# compute_module_USB.net
KiCad netlist of a schematic drawn in Altium Designer
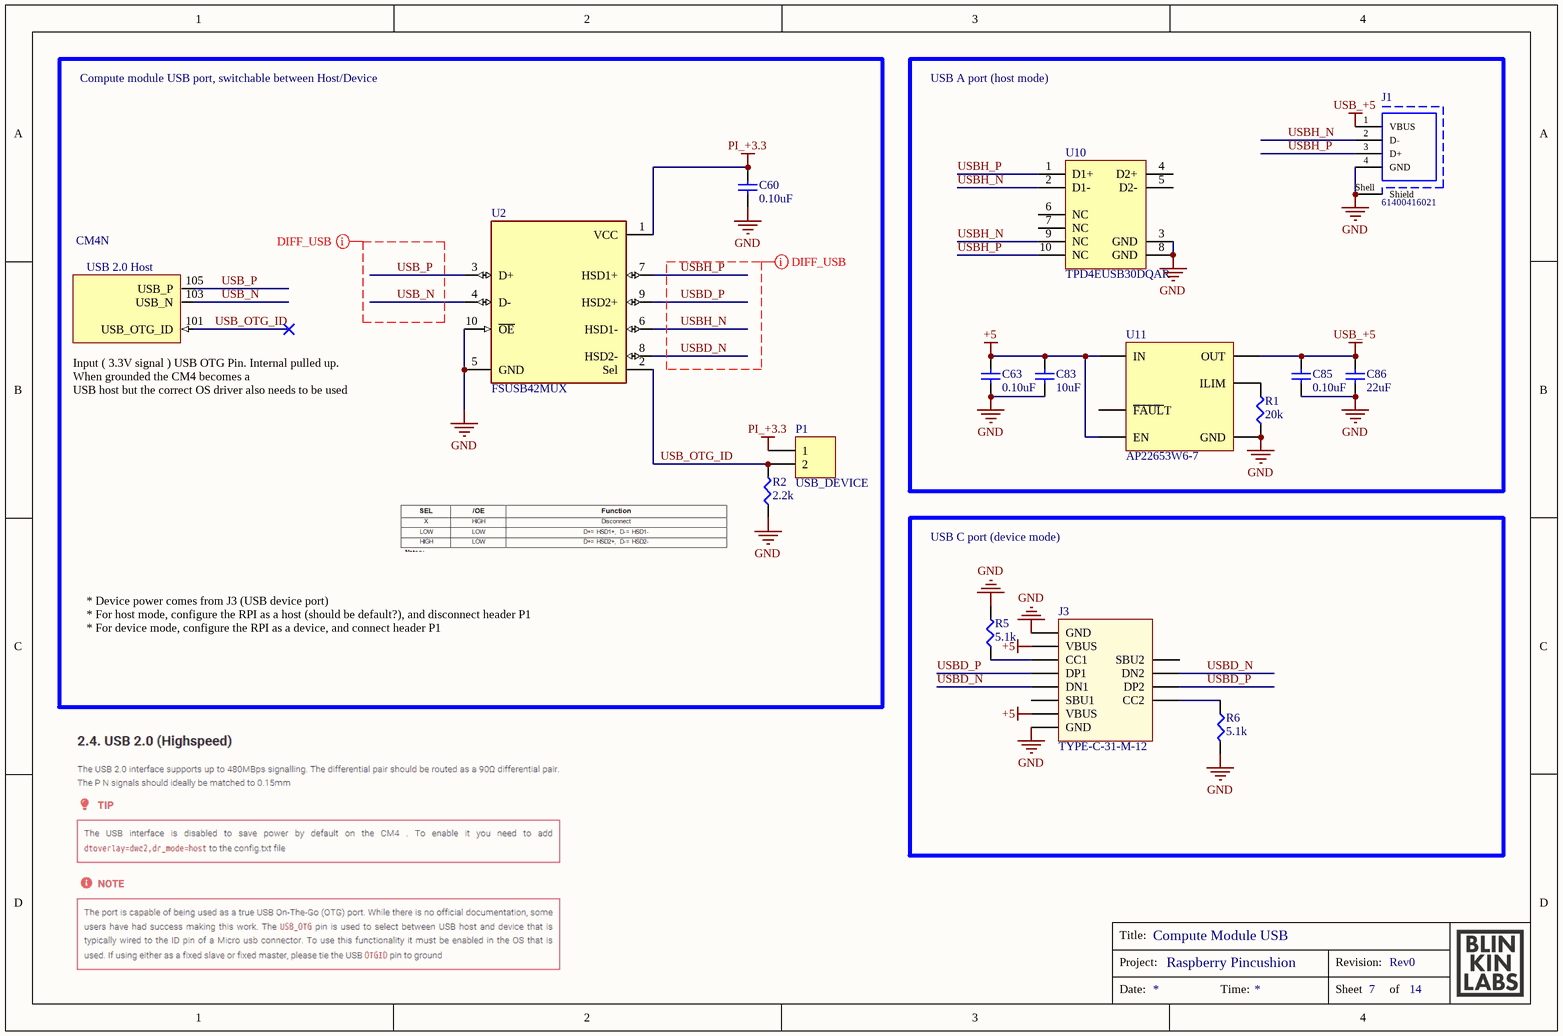
[diagram p0: compute module USB.SchDoc]

(export (version "E")
  (design (tool "Eeschema 10.0.6"))
  (components
    (comp (ref "C60")
      (value "0.10uF")
      (footprint "CAPC1005X06L")
      (description "CAP CER 0.1UF 10V X5R 0402")
      (fields
        (field (name "PARTNUMBER") "GRM155R61A104KA01D")
        (field (name "DIGI-KEY PART NUMBER") "490-1318-1-ND")
      )
      (libsource (lib "cap_murata") (part "CAPACITOR"))
    )
    (comp (ref "C63")
      (value "0.10uF")
      (footprint "CAPC1005X06L")
      (description "CAP CER 0.1UF 10V X5R 0402")
      (fields
        (field (name "PARTNUMBER") "GRM155R61A104KA01D")
        (field (name "DIGI-KEY PART NUMBER") "490-1318-1-ND")
      )
      (libsource (lib "cap_murata") (part "CAPACITOR"))
    )
    (comp (ref "C83")
      (value "10uF")
      (footprint "CAPC2012X10L")
      (description "CAP CER 10UF 10V X7R 0805")
      (fields
        (field (name "PARTNUMBER") "GRM21BR71A106KE51L")
        (field (name "DIGI-KEY PART NUMBER") "490-3905-1-ND")
      )
      (libsource (lib "cap_murata") (part "CAPACITOR"))
    )
    (comp (ref "C85")
      (value "0.10uF")
      (footprint "CAPC1005X06L")
      (description "CAP CER 0.1UF 10V X5R 0402")
      (fields
        (field (name "PARTNUMBER") "GRM155R61A104KA01D")
        (field (name "DIGI-KEY PART NUMBER") "490-1318-1-ND")
      )
      (libsource (lib "cap_murata") (part "CAPACITOR"))
    )
    (comp (ref "C86")
      (value "22uF")
      (footprint "CAPC2012X10L")
      (description "CAP CER 22UF 10V X5R 0805")
      (fields
        (field (name "PARTNUMBER") "GRM219R61A226MEA0D")
        (field (name "DIGI-KEY PART NUMBER") "490-9951-1-ND")
      )
      (libsource (lib "cap_murata") (part "CAPACITOR"))
    )
    (comp (ref "CM4")
      (value "Raspberry Pi Compute Module 4")
      (footprint "CM4-F40C-100DS-0.4v_1.5mm_0mm")
      (description "Raspberry Pi Compute Module 4 by Amornthep Phunsin")
      (libsource (lib "CM4") (part "CM4"))
    )
    (comp (ref "J1")
      (value "61400416021")
      (footprint "61400416021")
      (description "USB 2.0 Type A Receptacle WR-COM, Horizontal, THT")
      (fields (field (name "MANUFACTURER") "Wurth Elektronik") (field (name "PUBLISHER") "WurthElektronik"))
      (libsource (lib "Altium Content Vault") (part "WE-USB-4-1SHLD"))
    )
    (comp (ref "J3")
      (value "TYPE-C-31-M-12")
      (footprint "TYPE-C-31-M-12")
      (description "USB Connector TYPE-C-31-M-12 Female 16P SMD")
      (fields (field (name "MANUFACTURER") "HRO"))
      (libsource (lib "Blinkinlabs") (part "TYPE-C-31-M-12"))
    )
    (comp (ref "P1")
      (value "USB_DEVICE")
      (footprint "HDR1X2")
      (description "Header, 2-Pin")
      (fields (field (name "PUBLISHER") "Altium Limited"))
      (libsource (lib "Miscellaneous Connectors") (part "Header 2"))
    )
    (comp (ref "R1")
      (value "20k")
      (footprint "ERJ2G(0402)_L")
      (description "RES SMD 20K OHM 1% 1/10W 0402")
      (fields
        (field (name "PARTNUMBER") "ERJ-2RKF2002X")
        (field (name "DIGI-KEY PART NUMBER") "P20.0KLCT-ND")
      )
      (libsource (lib "res_panasonic_erj_xls") (part "RESISTOR"))
    )
    (comp (ref "R2")
      (value "2.2k")
      (footprint "ERJ2G(0402)_L")
      (description "RES SMD 2.2K OHM 1% 1/10W 0402")
      (fields
        (field (name "PARTNUMBER") "ERJ-2RKF2201X")
        (field (name "DIGI-KEY PART NUMBER") "P2.20KLCT-ND")
      )
      (libsource (lib "res_panasonic_erj_xls") (part "RESISTOR"))
    )
    (comp (ref "R5")
      (value "5.1k")
      (footprint "ERJ2G(0402)_N")
      (description "RES SMD 5.1K OHM 1% 1/10W 0402")
      (fields
        (field (name "PARTNUMBER") "ERJ-2RKF5101X")
        (field (name "DIGI-KEY PART NUMBER") "P5.10KLCT-ND")
      )
      (libsource (lib "res_panasonic_erj_xls") (part "RESISTOR"))
    )
    (comp (ref "R6")
      (value "5.1k")
      (footprint "ERJ2G(0402)_N")
      (description "RES SMD 5.1K OHM 1% 1/10W 0402")
      (fields
        (field (name "PARTNUMBER") "ERJ-2RKF5101X")
        (field (name "DIGI-KEY PART NUMBER") "P5.10KLCT-ND")
      )
      (libsource (lib "res_panasonic_erj_xls") (part "RESISTOR"))
    )
    (comp (ref "U2")
      (value "FSUSB42MUX")
      (footprint "FP-846AP-MFG")
      (description "IC USB SWITCH DPDT 10MSOP")
      (fields (field (name "VOLTAGE") "4.3V"))
      (libsource (lib "Altium Content Vault") (part "e0bd5e1b4e0e4edc77f3356c64bf8f9"))
    )
    (comp (ref "U10")
      (value "TPD4EUSB30DQAR")
      (footprint "DQA0010A_V")
      (fields (field (name "MANUFACTURER") "Texas Instruments"))
      (libsource (lib "Altium Content Vault") (part "TI-TPD4EUSB30-SON_DQA-10"))
    )
    (comp (ref "U11")
      (value "AP22653W6-7")
      (footprint "SOT95P280X145-6N-5")
      (description "LOAD SWITCH,SOT26,T&R,3K")
      (fields
        (field (name "MANUFACTURER") "Diodes Incorporated")
        (field (name "DIGIKEY PARTNUMBER") "31-AP22653W6-7TR-ND")
      )
      (libsource (lib "Blinkinlabs") (part "AP22653W6-7"))
    )
  )
  (nets
    (net (code "1") (name "+5") (class "Default")
      (node (ref "C63") (pin "2") (pinfunction "2_2") (pintype "passive"))
      (node (ref "C83") (pin "1") (pinfunction "1_1") (pintype "passive"))
      (node (ref "J3") (pin "A4/B9") (pinfunction "VBUS_A4/B9") (pintype "passive"))
      (node (ref "J3") (pin "A9/B4") (pinfunction "VBUS_A9/B4") (pintype "passive"))
      (node (ref "U11") (pin "1") (pinfunction "IN_1") (pintype "passive"))
      (node (ref "U11") (pin "3") (pinfunction "EN_3") (pintype "passive"))
    )
    (net (code "2") (name "/USBD_N") (class "Default")
      (node (ref "J3") (pin "A7") (pinfunction "DN1_A7") (pintype "passive"))
      (node (ref "J3") (pin "B7") (pinfunction "DN2_B7") (pintype "passive"))
      (node (ref "U2") (pin "8") (pinfunction "HSD2-_8") (pintype "bidirectional"))
    )
    (net (code "3") (name "/USBD_P") (class "Default")
      (node (ref "J3") (pin "A6") (pinfunction "DP1_A6") (pintype "passive"))
      (node (ref "J3") (pin "B6") (pinfunction "DP2_B6") (pintype "passive"))
      (node (ref "U2") (pin "9") (pinfunction "HSD2+_9") (pintype "bidirectional"))
    )
    (net (code "4") (name "/USBH_N") (class "Default")
      (node (ref "J1") (pin "2") (pinfunction "D-_2") (pintype "passive"))
      (node (ref "U10") (pin "2") (pinfunction "D1-_2") (pintype "passive"))
      (node (ref "U10") (pin "9") (pinfunction "NC_9") (pintype "passive"))
      (node (ref "U2") (pin "6") (pinfunction "HSD1-_6") (pintype "bidirectional"))
    )
    (net (code "5") (name "/USBH_P") (class "Default")
      (node (ref "J1") (pin "3") (pinfunction "D+_3") (pintype "passive"))
      (node (ref "U10") (pin "1") (pinfunction "D1+_1") (pintype "passive"))
      (node (ref "U10") (pin "10") (pinfunction "NC_10") (pintype "passive"))
      (node (ref "U2") (pin "7") (pinfunction "HSD1+_7") (pintype "bidirectional"))
    )
    (net (code "6") (name "/USB_N") (class "Default")
      (node (ref "CM4") (pin "103") (pinfunction "USB_N_103") (pintype "passive"))
      (node (ref "U2") (pin "4") (pinfunction "D-_4") (pintype "bidirectional"))
    )
    (net (code "7") (name "/USB_OTG_ID") (class "Default")
      (node (ref "CM4") (pin "101") (pinfunction "USB_OTG_ID_101") (pintype "input"))
      (node (ref "P1") (pin "2") (pinfunction "2_2") (pintype "passive"))
      (node (ref "R2") (pin "2") (pinfunction "2_2") (pintype "passive"))
      (node (ref "U2") (pin "2") (pinfunction "Sel_2") (pintype "passive"))
    )
    (net (code "8") (name "/USB_P") (class "Default")
      (node (ref "CM4") (pin "105") (pinfunction "USB_P_105") (pintype "passive"))
      (node (ref "U2") (pin "3") (pinfunction "D+_3") (pintype "bidirectional"))
    )
    (net (code "9") (name "GND") (class "Default")
      (node (ref "C60") (pin "1") (pinfunction "1_1") (pintype "passive"))
      (node (ref "C63") (pin "1") (pinfunction "1_1") (pintype "passive"))
      (node (ref "C83") (pin "2") (pinfunction "2_2") (pintype "passive"))
      (node (ref "C85") (pin "1") (pinfunction "1_1") (pintype "passive"))
      (node (ref "C86") (pin "2") (pinfunction "2_2") (pintype "passive"))
      (node (ref "J1") (pin "4") (pinfunction "GND_4") (pintype "passive"))
      (node (ref "J1") (pin "Shell") (pinfunction "Shield_Shell") (pintype "passive"))
      (node (ref "J3") (pin "A1/B12") (pinfunction "GND_A1/B12") (pintype "passive"))
      (node (ref "J3") (pin "A12/B1") (pinfunction "GND_A12/B1") (pintype "passive"))
      (node (ref "R1") (pin "1") (pinfunction "1_1") (pintype "passive"))
      (node (ref "R2") (pin "1") (pinfunction "1_1") (pintype "passive"))
      (node (ref "R5") (pin "2") (pinfunction "2_2") (pintype "passive"))
      (node (ref "R6") (pin "2") (pinfunction "2_2") (pintype "passive"))
      (node (ref "U10") (pin "3") (pinfunction "GND_3") (pintype "power_in"))
      (node (ref "U10") (pin "8") (pinfunction "GND_8") (pintype "power_in"))
      (node (ref "U11") (pin "2") (pinfunction "GND_2") (pintype "passive"))
      (node (ref "U2") (pin "10") (pinfunction "~{OE}_10") (pintype "input"))
      (node (ref "U2") (pin "5") (pinfunction "GND_5") (pintype "power_in"))
    )
    (net (code "10") (name "Net-(J3-CC1)") (class "Default")
      (node (ref "J3") (pin "A5") (pinfunction "CC1_A5") (pintype "passive"))
      (node (ref "R5") (pin "1") (pinfunction "1_1") (pintype "passive"))
    )
    (net (code "11") (name "Net-(J3-CC2)") (class "Default")
      (node (ref "J3") (pin "B5") (pinfunction "CC2_B5") (pintype "passive"))
      (node (ref "R6") (pin "1") (pinfunction "1_1") (pintype "passive"))
    )
    (net (code "12") (name "Net-(U11-ILIM)") (class "Default")
      (node (ref "R1") (pin "2") (pinfunction "2_2") (pintype "passive"))
      (node (ref "U11") (pin "5") (pinfunction "ILIM_5") (pintype "passive"))
    )
    (net (code "13") (name "PI_+3.3") (class "Default")
      (node (ref "C60") (pin "2") (pinfunction "2_2") (pintype "passive"))
      (node (ref "P1") (pin "1") (pinfunction "1_1") (pintype "passive"))
      (node (ref "U2") (pin "1") (pinfunction "VCC_1") (pintype "power_in"))
    )
    (net (code "14") (name "USB_+5") (class "Default")
      (node (ref "C85") (pin "2") (pinfunction "2_2") (pintype "passive"))
      (node (ref "C86") (pin "1") (pinfunction "1_1") (pintype "passive"))
      (node (ref "J1") (pin "1") (pinfunction "VBUS_1") (pintype "passive"))
      (node (ref "U11") (pin "6") (pinfunction "OUT_6") (pintype "passive"))
    )
    (net (code "15") (name "unconnected-(J3-SBU1-PadA8)") (class "Default")
      (node (ref "J3") (pin "A8") (pinfunction "SBU1_A8") (pintype "passive"))
    )
    (net (code "16") (name "unconnected-(J3-SBU2-PadB8)") (class "Default")
      (node (ref "J3") (pin "B8") (pinfunction "SBU2_B8") (pintype "passive"))
    )
    (net (code "17") (name "unconnected-(U10-D2+-Pad4)") (class "Default")
      (node (ref "U10") (pin "4") (pinfunction "D2+_4") (pintype "passive"))
    )
    (net (code "18") (name "unconnected-(U10-D2--Pad5)") (class "Default")
      (node (ref "U10") (pin "5") (pinfunction "D2-_5") (pintype "passive"))
    )
    (net (code "19") (name "unconnected-(U10-NC-Pad6)") (class "Default")
      (node (ref "U10") (pin "6") (pinfunction "NC_6") (pintype "passive"))
    )
    (net (code "20") (name "unconnected-(U10-NC-Pad7)") (class "Default")
      (node (ref "U10") (pin "7") (pinfunction "NC_7") (pintype "passive"))
    )
    (net (code "21") (name "unconnected-(U11-~{FAUL}T-Pad4)") (class "Default")
      (node (ref "U11") (pin "4") (pinfunction "~{FAUL}T_4") (pintype "passive"))
    )
  )
)
